# Sheet1.net
KiCad netlist of a schematic drawn in Altium Designer
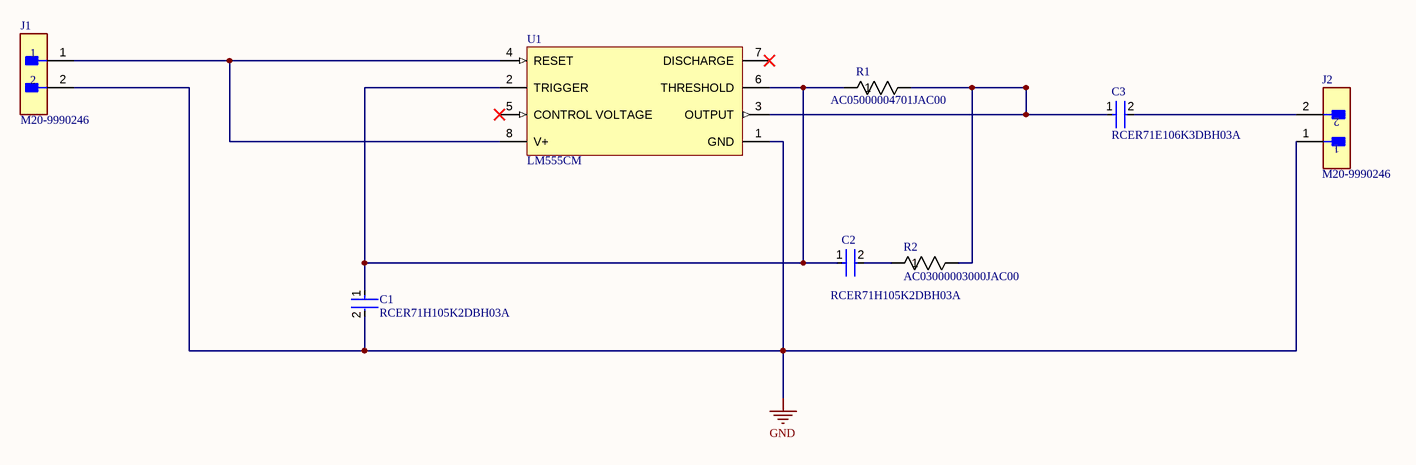
[diagram p0: Sheet1.SchDoc]

(export (version "E")
  (design (tool "Eeschema 10.0.6"))
  (components
    (comp (ref "C1")
      (value "RCER71H105K2DBH03A")
      (footprint "FP-RCE2A2-MFG")
      (description "Cap Ceramic 1uF 50V X7R ±10% Radial 2.5mm +125°C Automotive Ammo Pack")
      (fields (field (name "TOLERANCE") "10%"))
      (libsource (lib "Altium Content Vault") (part "b4654b650e69147ec39a6b967a45e02"))
    )
    (comp (ref "C2")
      (value "RCER71H105K2DBH03A")
      (footprint "FP-RCE2A2-MFG")
      (description "Cap Ceramic 1uF 50V X7R ±10% Radial 2.5mm +125°C Automotive Ammo Pack")
      (fields (field (name "TOLERANCE") "10%"))
      (libsource (lib "Altium Content Vault") (part "b4654b650e69147ec39a6b967a45e02"))
    )
    (comp (ref "C3")
      (value "RCER71E106K3DBH03A")
      (footprint "FP-RCE3DB-MFG")
      (description "Cap Ceramic 10uF 25V X7R ±10% Radial 2.5mm +125°C Automotive Ammo Pack")
      (fields (field (name "TOLERANCE") "10%"))
      (libsource (lib "Altium Content Vault") (part "b4654b650e69147ec39a6b967a45e02"))
    )
    (comp (ref "J1")
      (value "M20-9990246")
      (footprint "FP-M20-9990246-MFG")
      (description "Connector Header Through Hole 2 position 0.100\" (2.54mm)")
      (fields (field (name "OCTOPART") "https://octopart.com/m20-9990246-harwin-2590635"))
      (libsource (lib "") (part "3bc925449376181038e59eaffc5286c_1"))
    )
    (comp (ref "J2")
      (value "M20-9990246")
      (footprint "FP-M20-9990246-MFG")
      (description "Connector Header Through Hole 2 position 0.100\" (2.54mm)")
      (fields (field (name "OCTOPART") "https://octopart.com/m20-9990246-harwin-2590635"))
      (libsource (lib "Altium Content Vault") (part "3bc925449376181038e59eaffc5286c"))
    )
    (comp (ref "R1")
      (value "AC05000004701JAC00")
      (footprint "RES_AC05_VIS")
      (fields (field (name "TOLERANCE") "5%"))
      (libsource (lib "Altium Content Vault") (part "AC05000004701JAC00"))
    )
    (comp (ref "R2")
      (value "AC03000003000JAC00")
      (footprint "RES_AC03_VIS")
      (fields (field (name "TOLERANCE") "5%"))
      (libsource (lib "Altium Content Vault") (part "AC03000003000JAC00"))
    )
    (comp (ref "U1")
      (value "LM555CM")
      (footprint "D0008A_M")
      (fields (field (name "MANUFACTURER") "Texas Instruments (TI)") (field (name "POWER") "1.18W"))
      (libsource (lib "Ibrahim Khalid") (part "TI-LM555-8"))
    )
  )
  (nets
    (net (code "1") (name "GND") (class "Default")
      (node (ref "C1") (pin "2") (pinfunction "2_2") (pintype "passive"))
      (node (ref "J1") (pin "2") (pinfunction "2_2") (pintype "passive"))
      (node (ref "J2") (pin "1") (pinfunction "1_1") (pintype "passive"))
      (node (ref "U1") (pin "1") (pinfunction "GND_1") (pintype "power_in"))
    )
    (net (code "2") (name "Net-(C2-Pad2)") (class "Default")
      (node (ref "C2") (pin "2") (pinfunction "2_2") (pintype "passive"))
      (node (ref "R2") (pin "1") (pinfunction "1_1") (pintype "passive"))
    )
    (net (code "3") (name "Net-(C3-Pad2)") (class "Default")
      (node (ref "C3") (pin "2") (pinfunction "2_2") (pintype "passive"))
      (node (ref "J2") (pin "2") (pinfunction "2_2") (pintype "passive"))
    )
    (net (code "4") (name "Net-(U1-OUTPUT)") (class "Default")
      (node (ref "C3") (pin "1") (pinfunction "1_1") (pintype "passive"))
      (node (ref "R1") (pin "2") (pinfunction "2_2") (pintype "passive"))
      (node (ref "R2") (pin "2") (pinfunction "2_2") (pintype "passive"))
      (node (ref "U1") (pin "3") (pinfunction "OUTPUT_3") (pintype "output"))
    )
    (net (code "5") (name "Net-(U1-RESET)") (class "Default")
      (node (ref "J1") (pin "1") (pinfunction "1_1") (pintype "passive"))
      (node (ref "U1") (pin "4") (pinfunction "RESET_4") (pintype "input"))
      (node (ref "U1") (pin "8") (pinfunction "V+_8") (pintype "power_in"))
    )
    (net (code "6") (name "Net-(U1-THRESHOLD)") (class "Default")
      (node (ref "C1") (pin "1") (pinfunction "1_1") (pintype "passive"))
      (node (ref "C2") (pin "1") (pinfunction "1_1") (pintype "passive"))
      (node (ref "R1") (pin "1") (pinfunction "1_1") (pintype "passive"))
      (node (ref "U1") (pin "2") (pinfunction "TRIGGER_2") (pintype "passive"))
      (node (ref "U1") (pin "6") (pinfunction "THRESHOLD_6") (pintype "passive"))
    )
    (net (code "7") (name "unconnected-(U1-CONTROL_VOLTAGE-Pad5)") (class "Default")
      (node (ref "U1") (pin "5") (pinfunction "CONTROL_VOLTAGE_5") (pintype "input+no_connect"))
    )
    (net (code "8") (name "unconnected-(U1-DISCHARGE-Pad7)") (class "Default")
      (node (ref "U1") (pin "7") (pinfunction "DISCHARGE_7") (pintype "open_collector+no_connect"))
    )
  )
)
